# SCH_SAO-ctf-2024_2024-02-07.net
KiCad netlist of a schematic drawn in EasyEDA
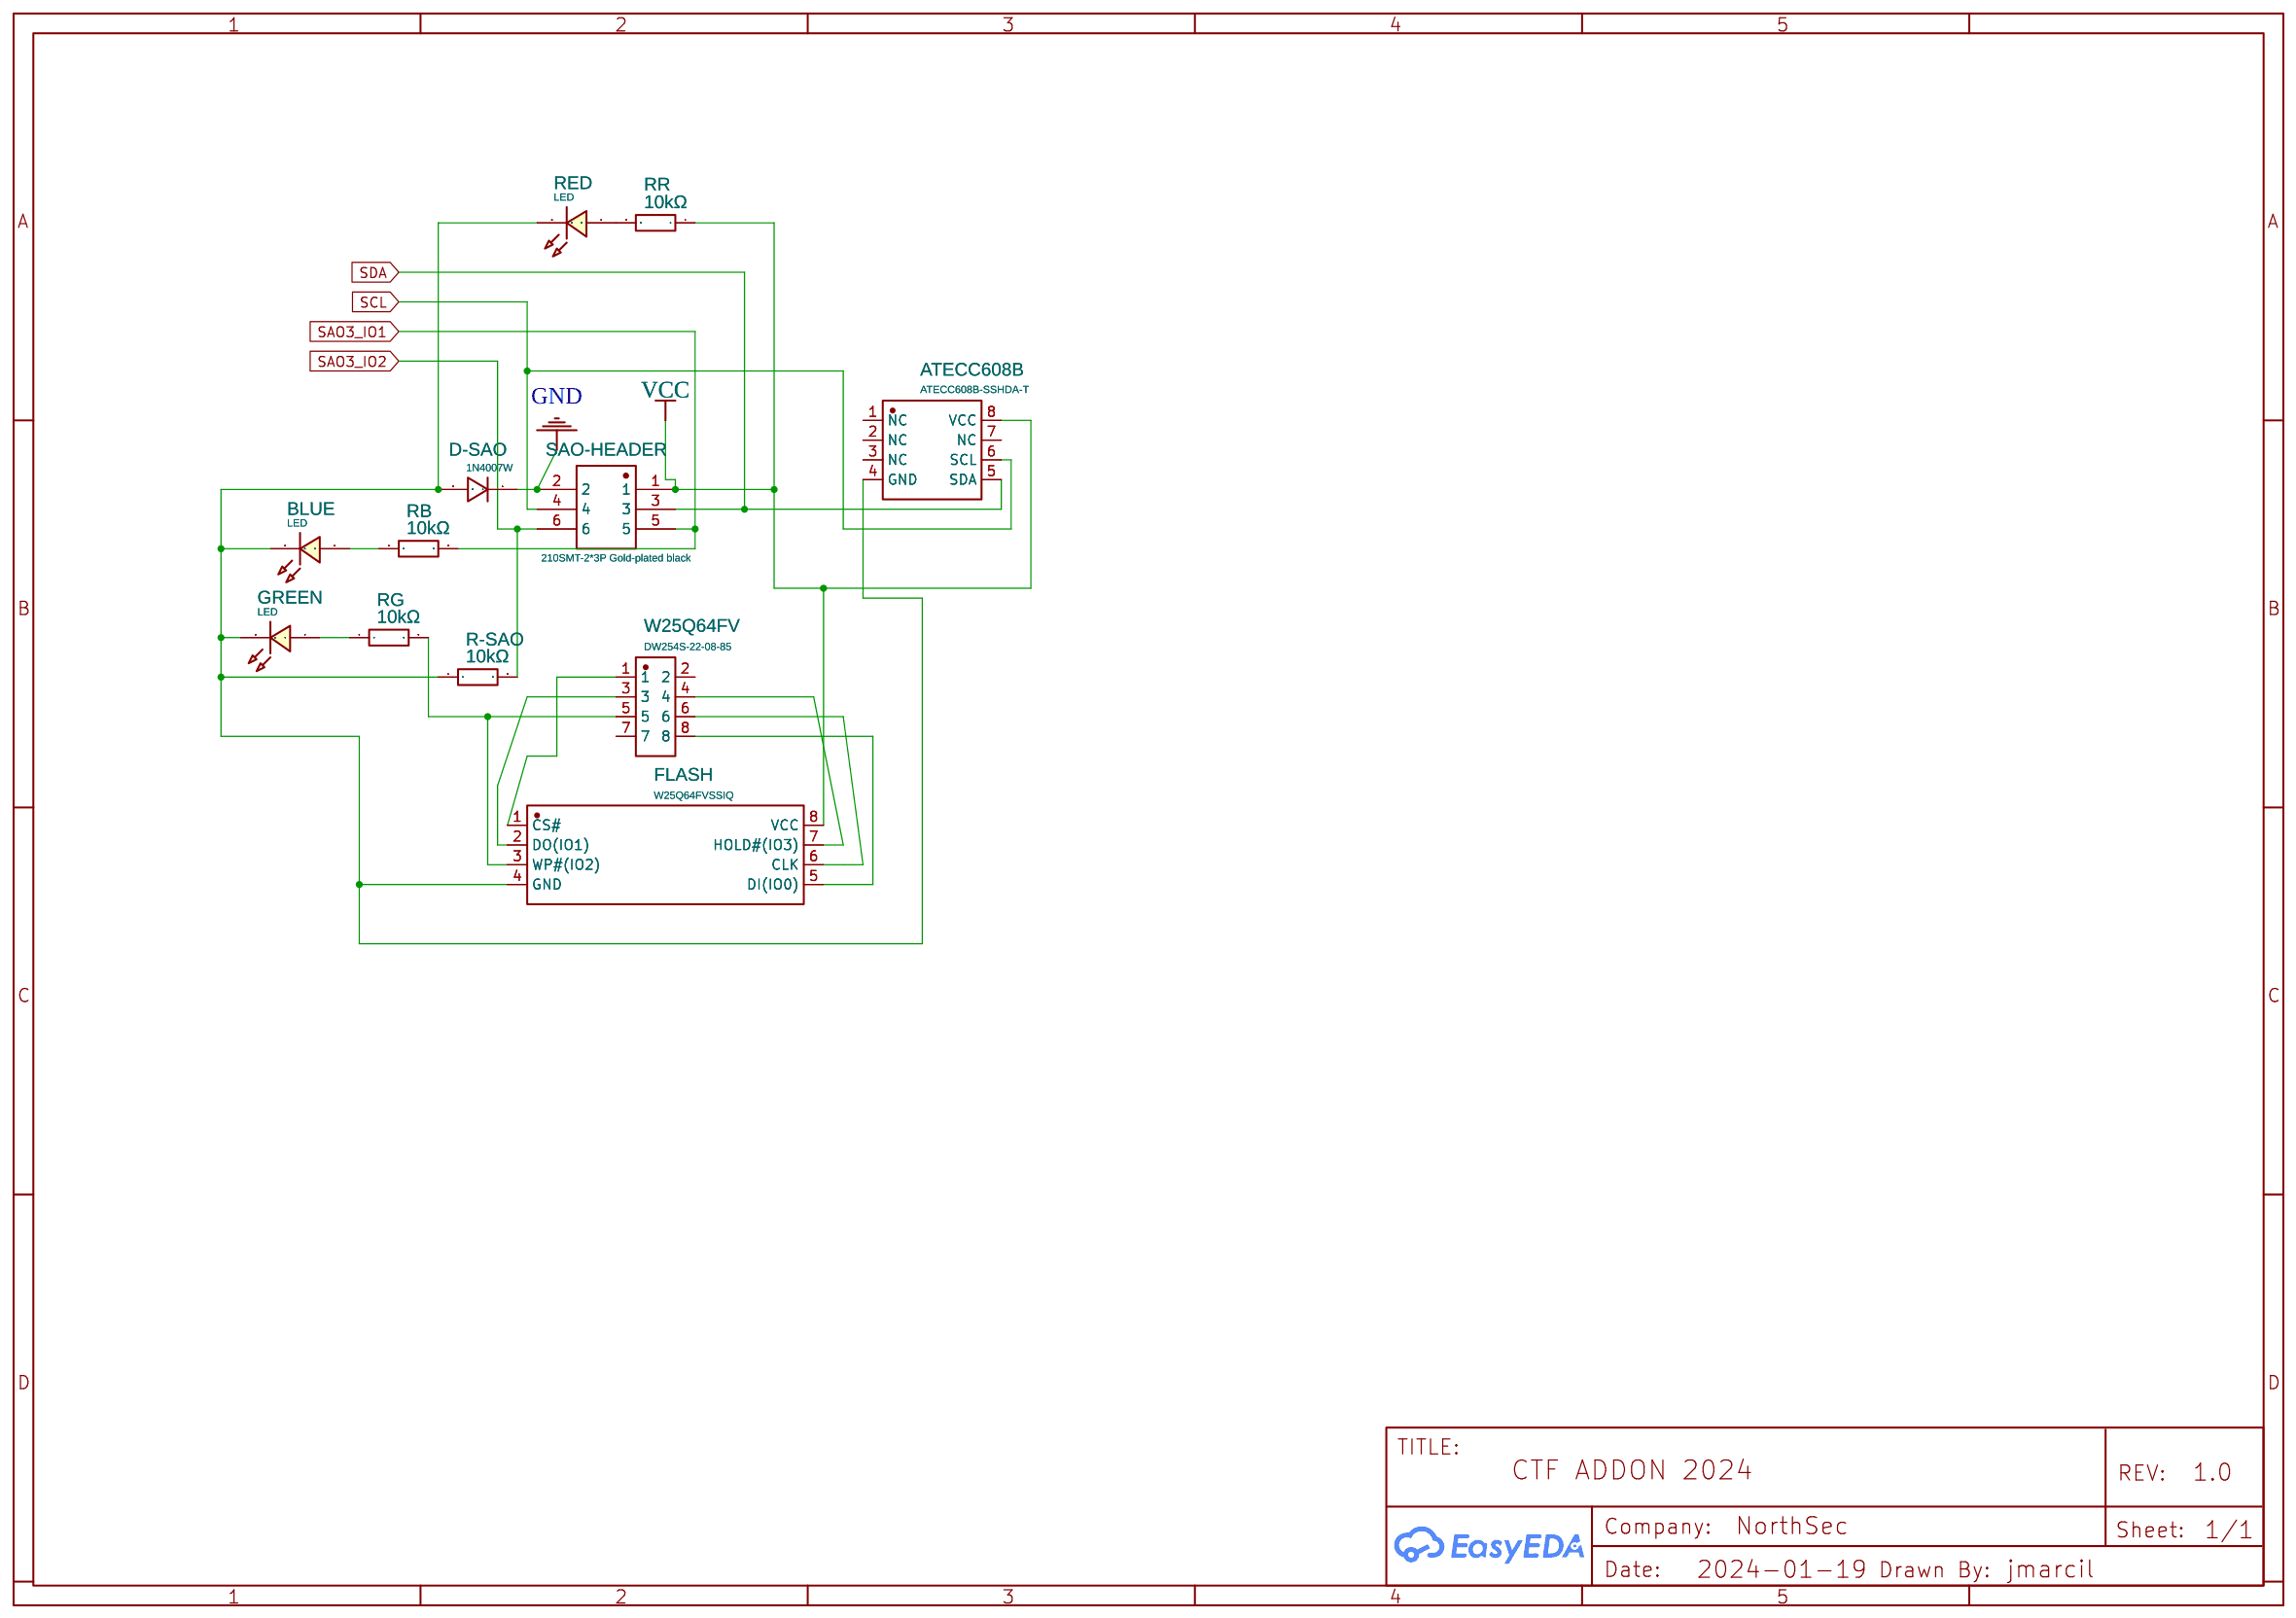
[diagram p0: schematic sheet]

(export (version "E")
  (design (tool "Eeschema 10.0.6"))
  (components
    (comp (ref "ATECC608B")
      (value "ATECC608B-SSHDA-T")
      (fields (field (name "Manufacturer") "MICROCHIP(美国微芯)"))
      (libsource (lib "") (part "ATECC608B-SSHDA-T"))
    )
    (comp (ref "BLUE")
      (value "LED")
      (fields
        (field (name "Manufacturer Part") "19-217/BHC-ZL1M2RY/3T")
        (field (name "Manufacturer") "EVERLIGHT(台湾亿光)")
      )
      (libsource (lib "") (part "LED-0603_B"))
    )
    (comp (ref "D-SAO")
      (value "1N4007W")
      (fields (field (name "Manufacturer") "BLUE ROCKET"))
      (libsource (lib "") (part "1N4007W"))
    )
    (comp (ref "FLASH")
      (value "W25Q64FVSSIQ")
      (fields (field (name "Manufacturer") "WINBOND(华邦)"))
      (libsource (lib "") (part "W25Q64FVSSIQ"))
    )
    (comp (ref "GREEN")
      (value "LED")
      (fields
        (field (name "Manufacturer Part") "19-217/GHC-YR1S2/3T")
        (field (name "Manufacturer") "EVERLIGHT(台湾亿光)")
      )
      (libsource (lib "") (part "LED-0603_G"))
    )
    (comp (ref "R-SAO")
      (value "10kΩ")
      (fields
        (field (name "Manufacturer Part") "1206W4F1002T5E")
        (field (name "Manufacturer") "UNI-ROYAL(厚声)")
      )
      (libsource (lib "") (part "1206W4F1002T5E_2"))
    )
    (comp (ref "RB")
      (value "10kΩ")
      (fields
        (field (name "Manufacturer Part") "1206W4F1002T5E")
        (field (name "Manufacturer") "UNI-ROYAL(厚声)")
      )
      (libsource (lib "") (part "1206W4F1002T5E_1"))
    )
    (comp (ref "RED")
      (value "LED")
      (fields
        (field (name "Manufacturer Part") "19-217/R6C-AL1M2VY/3T")
        (field (name "Manufacturer") "EVERLIGHT(台湾亿光)")
      )
      (libsource (lib "") (part "LED-0603_R"))
    )
    (comp (ref "RG")
      (value "10kΩ")
      (fields
        (field (name "Manufacturer Part") "1206W4F1002T5E")
        (field (name "Manufacturer") "UNI-ROYAL(厚声)")
      )
      (libsource (lib "") (part "1206W4F1002T5E"))
    )
    (comp (ref "RR")
      (value "10kΩ")
      (fields
        (field (name "Manufacturer Part") "1206W4F1002T5E")
        (field (name "Manufacturer") "UNI-ROYAL(厚声)")
      )
      (libsource (lib "") (part "1206W4F1002T5E_3"))
    )
    (comp (ref "SAO-HEADER")
      (value "210SMT-2*3P Gold-plated black")
      (fields (field (name "Manufacturer Part") "B-2100N06P-B111") (field (name "Manufacturer") "Ckmtw(灿科盟)"))
      (libsource (lib "") (part "210SMT-2*3P Gold-plated black"))
    )
    (comp (ref "W25Q64FV")
      (value "DW254S-22-08-85")
      (fields (field (name "Manufacturer") "DEALON(德艺隆)"))
      (libsource (lib "") (part "DW254S-22-08-85"))
    )
  )
  (nets
    (net (code "1") (name "GND") (class "Default")
      (node (ref "D-SAO") (pin "1") (pinfunction "1_1") (pintype "unspecified"))
      (node (ref "SAO-HEADER") (pin "2") (pinfunction "2_2") (pintype "unspecified"))
    )
    (net (code "2") (name "Net-(ATECC608B-GND)") (class "Default")
      (node (ref "ATECC608B") (pin "4") (pinfunction "GND_4") (pintype "unspecified"))
      (node (ref "BLUE") (pin "2") (pinfunction "2_2") (pintype "unspecified"))
      (node (ref "D-SAO") (pin "2") (pinfunction "2_2") (pintype "unspecified"))
      (node (ref "FLASH") (pin "4") (pinfunction "GND_4") (pintype "unspecified"))
      (node (ref "GREEN") (pin "2") (pinfunction "2_2") (pintype "unspecified"))
      (node (ref "R-SAO") (pin "1") (pinfunction "1_1") (pintype "input"))
      (node (ref "RED") (pin "2") (pinfunction "2_2") (pintype "unspecified"))
    )
    (net (code "3") (name "Net-(BLUE-Pad1)") (class "Default")
      (node (ref "BLUE") (pin "1") (pinfunction "1_1") (pintype "unspecified"))
      (node (ref "RB") (pin "1") (pinfunction "1_1") (pintype "input"))
    )
    (net (code "4") (name "Net-(FLASH-CLK)") (class "Default")
      (node (ref "FLASH") (pin "6") (pinfunction "CLK_6") (pintype "unspecified"))
      (node (ref "W25Q64FV") (pin "6") (pinfunction "6_6") (pintype "unspecified"))
    )
    (net (code "5") (name "Net-(FLASH-CS#)") (class "Default")
      (node (ref "FLASH") (pin "1") (pinfunction "CS#_1") (pintype "unspecified"))
      (node (ref "W25Q64FV") (pin "1") (pinfunction "1_1") (pintype "unspecified"))
    )
    (net (code "6") (name "Net-(FLASH-DI(IO0))") (class "Default")
      (node (ref "FLASH") (pin "5") (pinfunction "DI(IO0)_5") (pintype "unspecified"))
      (node (ref "W25Q64FV") (pin "8") (pinfunction "8_8") (pintype "unspecified"))
    )
    (net (code "7") (name "Net-(FLASH-DO(IO1))") (class "Default")
      (node (ref "FLASH") (pin "2") (pinfunction "DO(IO1)_2") (pintype "unspecified"))
      (node (ref "W25Q64FV") (pin "3") (pinfunction "3_3") (pintype "unspecified"))
    )
    (net (code "8") (name "Net-(FLASH-HOLD#(IO3))") (class "Default")
      (node (ref "FLASH") (pin "7") (pinfunction "HOLD#(IO3)_7") (pintype "unspecified"))
      (node (ref "W25Q64FV") (pin "4") (pinfunction "4_4") (pintype "unspecified"))
    )
    (net (code "9") (name "Net-(FLASH-WP#(IO2))") (class "Default")
      (node (ref "FLASH") (pin "3") (pinfunction "WP#(IO2)_3") (pintype "unspecified"))
      (node (ref "RG") (pin "2") (pinfunction "2_2") (pintype "input"))
      (node (ref "W25Q64FV") (pin "5") (pinfunction "5_5") (pintype "unspecified"))
    )
    (net (code "10") (name "Net-(GREEN-Pad1)") (class "Default")
      (node (ref "GREEN") (pin "1") (pinfunction "1_1") (pintype "unspecified"))
      (node (ref "RG") (pin "1") (pinfunction "1_1") (pintype "input"))
    )
    (net (code "11") (name "Net-(RED-Pad1)") (class "Default")
      (node (ref "RED") (pin "1") (pinfunction "1_1") (pintype "unspecified"))
      (node (ref "RR") (pin "2") (pinfunction "2_2") (pintype "input"))
    )
    (net (code "12") (name "SAO3_IO1") (class "Default")
      (node (ref "RB") (pin "2") (pinfunction "2_2") (pintype "input"))
      (node (ref "SAO-HEADER") (pin "5") (pinfunction "5_5") (pintype "unspecified"))
    )
    (net (code "13") (name "SAO3_IO2") (class "Default")
      (node (ref "R-SAO") (pin "2") (pinfunction "2_2") (pintype "input"))
      (node (ref "SAO-HEADER") (pin "6") (pinfunction "6_6") (pintype "unspecified"))
    )
    (net (code "14") (name "SCL") (class "Default")
      (node (ref "ATECC608B") (pin "6") (pinfunction "SCL_6") (pintype "unspecified"))
      (node (ref "SAO-HEADER") (pin "4") (pinfunction "4_4") (pintype "unspecified"))
    )
    (net (code "15") (name "SDA") (class "Default")
      (node (ref "ATECC608B") (pin "5") (pinfunction "SDA_5") (pintype "unspecified"))
      (node (ref "SAO-HEADER") (pin "3") (pinfunction "3_3") (pintype "unspecified"))
    )
    (net (code "16") (name "VCC") (class "Default")
      (node (ref "ATECC608B") (pin "8") (pinfunction "VCC_8") (pintype "unspecified"))
      (node (ref "FLASH") (pin "8") (pinfunction "VCC_8") (pintype "unspecified"))
      (node (ref "RR") (pin "1") (pinfunction "1_1") (pintype "input"))
      (node (ref "SAO-HEADER") (pin "1") (pinfunction "1_1") (pintype "unspecified"))
    )
    (net (code "17") (name "unconnected-(ATECC608B-NC-Pad1)") (class "Default")
      (node (ref "ATECC608B") (pin "1") (pinfunction "NC_1") (pintype "unspecified"))
    )
    (net (code "18") (name "unconnected-(ATECC608B-NC-Pad2)") (class "Default")
      (node (ref "ATECC608B") (pin "2") (pinfunction "NC_2") (pintype "unspecified"))
    )
    (net (code "19") (name "unconnected-(ATECC608B-NC-Pad3)") (class "Default")
      (node (ref "ATECC608B") (pin "3") (pinfunction "NC_3") (pintype "unspecified"))
    )
    (net (code "20") (name "unconnected-(ATECC608B-NC-Pad7)") (class "Default")
      (node (ref "ATECC608B") (pin "7") (pinfunction "NC_7") (pintype "unspecified"))
    )
    (net (code "21") (name "unconnected-(W25Q64FV-Pad2)") (class "Default")
      (node (ref "W25Q64FV") (pin "2") (pinfunction "2_2") (pintype "unspecified"))
    )
    (net (code "22") (name "unconnected-(W25Q64FV-Pad7)") (class "Default")
      (node (ref "W25Q64FV") (pin "7") (pinfunction "7_7") (pintype "unspecified"))
    )
  )
)
